# Audio_Codec_Analog_FrontEnd.net
KiCad netlist of a schematic drawn in Altium Designer
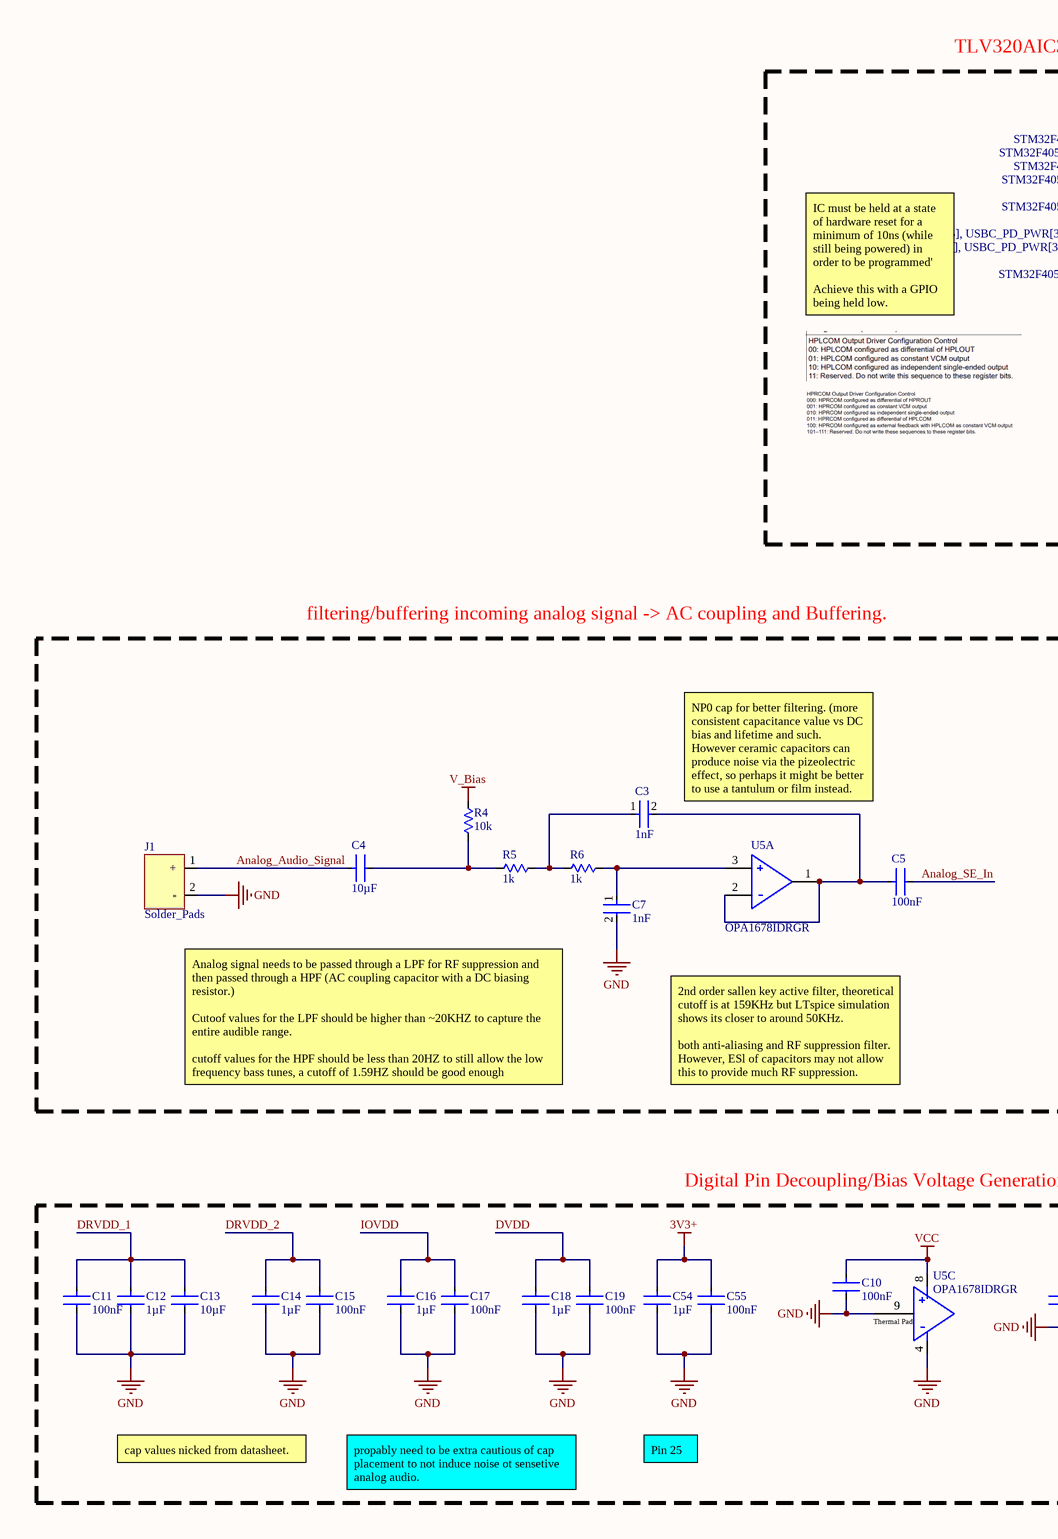
[diagram p0: Audio_Codec_Analog_FrontEnd.SchDoc, left]
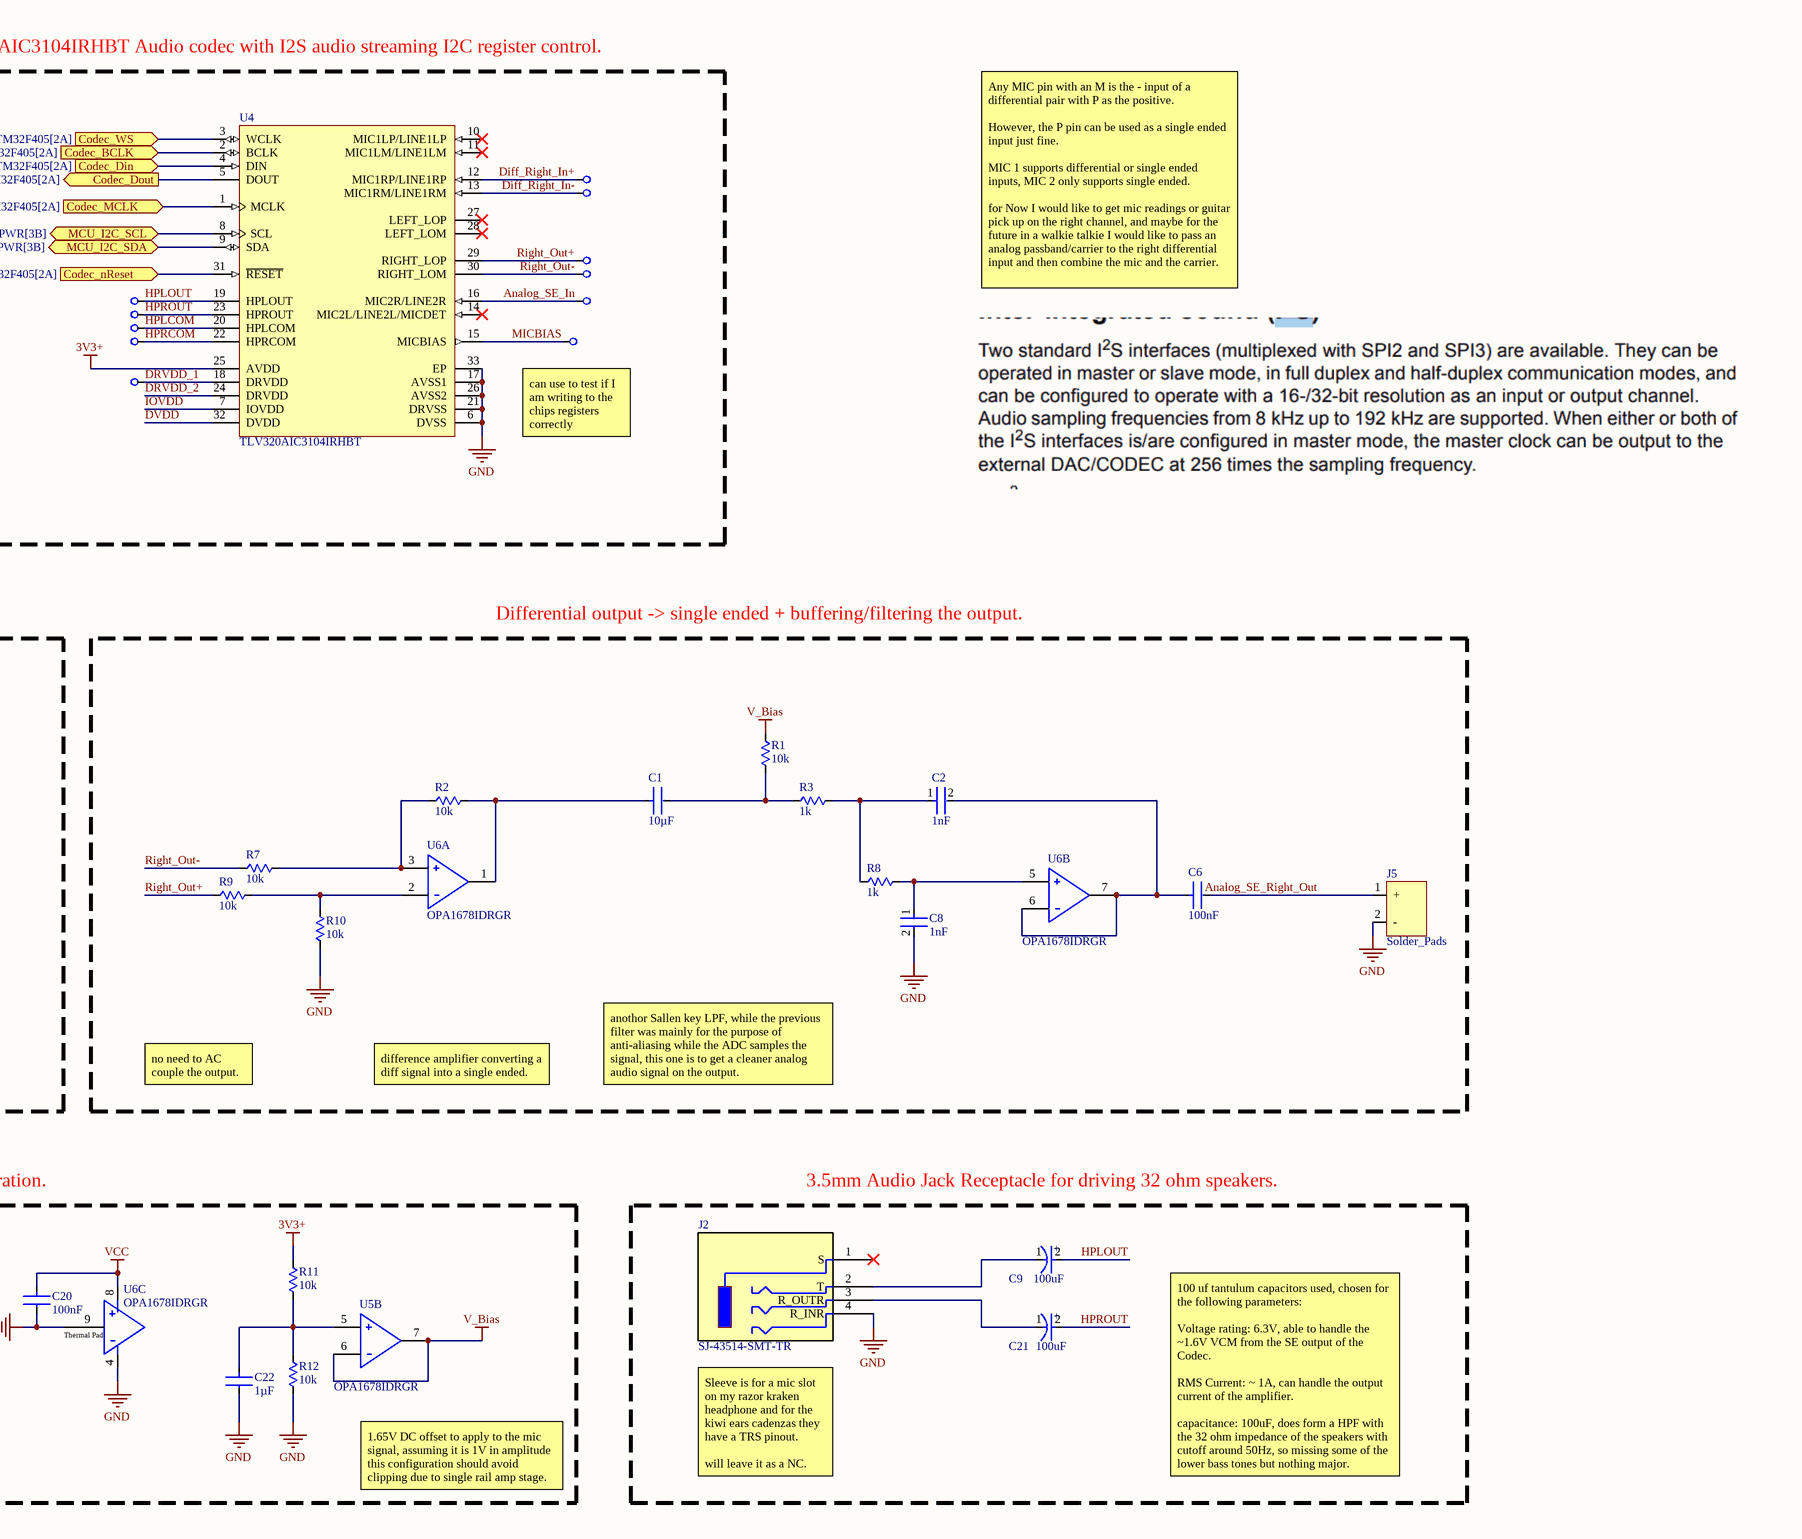
[diagram p1: Audio_Codec_Analog_FrontEnd.SchDoc, right]

(export (version "E")
  (design (tool "Eeschema 10.0.6"))
  (components
    (comp (ref "C1")
      (value "10µF")
      (footprint "MURATA-G_M21B")
      (description "10 µF ±10% 25V Ceramic Capacitor X7S 0805 (2012 Metric)")
      (fields (field (name "TOLERANCE") "10%") (field (name "Comment") "GCM21BC71E106KE36L"))
      (libsource (lib "UCalgary Racing") (part "CAPACITOR"))
    )
    (comp (ref "C2")
      (value "1nF")
      (footprint "FP-GRM188-0_1-e0_2_0_5-IPC_C")
      (description "Chip Multilayer Ceramic Capacitors for General Purpose, 0603, 1000pF, C0G, 30ppm/°C, 5%, 50V")
      (fields (field (name "TOLERANCE") "5%") (field (name "VOLTAGE") "50V"))
      (libsource (lib "Altium Content Vault") (part "11868f565c42a9108669ba33697ecf6"))
    )
    (comp (ref "C3")
      (value "1nF")
      (footprint "FP-GRM188-0_1-e0_2_0_5-IPC_C")
      (description "Chip Multilayer Ceramic Capacitors for General Purpose, 0603, 1000pF, C0G, 30ppm/°C, 5%, 50V")
      (fields (field (name "TOLERANCE") "5%") (field (name "VOLTAGE") "50V"))
      (libsource (lib "Altium Content Vault") (part "11868f565c42a9108669ba33697ecf6"))
    )
    (comp (ref "C4")
      (value "10µF")
      (footprint "MURATA-G_M21B")
      (description "10 µF ±10% 25V Ceramic Capacitor X7S 0805 (2012 Metric)")
      (fields (field (name "TOLERANCE") "10%") (field (name "Comment") "GCM21BC71E106KE36L"))
      (libsource (lib "UCalgary Racing") (part "CAPACITOR"))
    )
    (comp (ref "C5")
      (value "100nF")
      (footprint "MURATA-G_M188")
      (description "0.1 µF ±10% 50V Ceramic Capacitor X7R 0603 (1608 Metric)")
      (fields (field (name "TOLERANCE") "10%") (field (name "Comment") "GCM188R71H104KA57D"))
      (libsource (lib "UCalgary Racing") (part "CAPACITOR"))
    )
    (comp (ref "C6")
      (value "100nF")
      (footprint "MURATA-G_M188")
      (description "0.1 µF ±10% 50V Ceramic Capacitor X7R 0603 (1608 Metric)")
      (fields (field (name "TOLERANCE") "10%") (field (name "Comment") "GCM188R71H104KA57D"))
      (libsource (lib "UCalgary Racing") (part "CAPACITOR"))
    )
    (comp (ref "C7")
      (value "1nF")
      (footprint "FP-GRM188-0_1-e0_2_0_5-IPC_C")
      (description "Chip Multilayer Ceramic Capacitors for General Purpose, 0603, 1000pF, C0G, 30ppm/°C, 5%, 50V")
      (fields (field (name "TOLERANCE") "5%") (field (name "VOLTAGE") "50V"))
      (libsource (lib "Altium Content Vault") (part "11868f565c42a9108669ba33697ecf6"))
    )
    (comp (ref "C8")
      (value "1nF")
      (footprint "FP-GRM188-0_1-e0_2_0_5-IPC_C")
      (description "Chip Multilayer Ceramic Capacitors for General Purpose, 0603, 1000pF, C0G, 30ppm/°C, 5%, 50V")
      (fields (field (name "TOLERANCE") "5%") (field (name "VOLTAGE") "50V"))
      (libsource (lib "Altium Content Vault") (part "11868f565c42a9108669ba33697ecf6"))
    )
    (comp (ref "C9")
      (value "TAJB107M006RNJ")
      (footprint "FP-TAJB-MFG")
      (description "100uF 6.3V  ±20% 1.7Ω 1210  SMD Tantalum Capacitor")
      (fields (field (name "CAPACITANCE") "100uF") (field (name "TOLERANCE") "20%"))
      (libsource (lib "Altium Content Vault") (part "203bc49f2ac43e59fd269a8c329ed05"))
    )
    (comp (ref "C10")
      (value "100nF")
      (footprint "MURATA-G_M188")
      (description "0.1 µF ±10% 50V Ceramic Capacitor X7R 0603 (1608 Metric)")
      (fields (field (name "TOLERANCE") "10%") (field (name "Comment") "GCM188R71H104KA57D"))
      (libsource (lib "UCalgary Racing") (part "CAPACITOR"))
    )
    (comp (ref "C11")
      (value "100nF")
      (footprint "MURATA-G_M188")
      (description "0.1 µF ±10% 50V Ceramic Capacitor X7R 0603 (1608 Metric)")
      (fields (field (name "TOLERANCE") "10%") (field (name "Comment") "GCM188R71H104KA57D"))
      (libsource (lib "UCalgary Racing") (part "CAPACITOR"))
    )
    (comp (ref "C12")
      (value "1µF")
      (footprint "MURATA-G_M188")
      (description "1 µF ±10% 25V Ceramic Capacitor X7R 0603 (1608 Metric)")
      (fields (field (name "TOLERANCE") "10%") (field (name "Comment") "GCM188R71E105KA64D"))
      (libsource (lib "UCalgary Racing") (part "CAPACITOR"))
    )
    (comp (ref "C13")
      (value "10µF")
      (footprint "MURATA-G_M21B")
      (description "10 µF ±10% 25V Ceramic Capacitor X7S 0805 (2012 Metric)")
      (fields (field (name "TOLERANCE") "10%") (field (name "Comment") "GCM21BC71E106KE36L"))
      (libsource (lib "UCalgary Racing") (part "CAPACITOR"))
    )
    (comp (ref "C14")
      (value "1µF")
      (footprint "MURATA-G_M188")
      (description "1 µF ±10% 25V Ceramic Capacitor X7R 0603 (1608 Metric)")
      (fields (field (name "TOLERANCE") "10%") (field (name "Comment") "GCM188R71E105KA64D"))
      (libsource (lib "UCalgary Racing") (part "CAPACITOR"))
    )
    (comp (ref "C15")
      (value "100nF")
      (footprint "MURATA-G_M188")
      (description "0.1 µF ±10% 50V Ceramic Capacitor X7R 0603 (1608 Metric)")
      (fields (field (name "TOLERANCE") "10%") (field (name "Comment") "GCM188R71H104KA57D"))
      (libsource (lib "UCalgary Racing") (part "CAPACITOR"))
    )
    (comp (ref "C16")
      (value "1µF")
      (footprint "MURATA-G_M188")
      (description "1 µF ±10% 25V Ceramic Capacitor X7R 0603 (1608 Metric)")
      (fields (field (name "TOLERANCE") "10%") (field (name "Comment") "GCM188R71E105KA64D"))
      (libsource (lib "UCalgary Racing") (part "CAPACITOR"))
    )
    (comp (ref "C17")
      (value "100nF")
      (footprint "MURATA-G_M188")
      (description "0.1 µF ±10% 50V Ceramic Capacitor X7R 0603 (1608 Metric)")
      (fields (field (name "TOLERANCE") "10%") (field (name "Comment") "GCM188R71H104KA57D"))
      (libsource (lib "UCalgary Racing") (part "CAPACITOR"))
    )
    (comp (ref "C18")
      (value "1µF")
      (footprint "MURATA-G_M188")
      (description "1 µF ±10% 25V Ceramic Capacitor X7R 0603 (1608 Metric)")
      (fields (field (name "TOLERANCE") "10%") (field (name "Comment") "GCM188R71E105KA64D"))
      (libsource (lib "UCalgary Racing") (part "CAPACITOR"))
    )
    (comp (ref "C19")
      (value "100nF")
      (footprint "MURATA-G_M188")
      (description "0.1 µF ±10% 50V Ceramic Capacitor X7R 0603 (1608 Metric)")
      (fields (field (name "TOLERANCE") "10%") (field (name "Comment") "GCM188R71H104KA57D"))
      (libsource (lib "UCalgary Racing") (part "CAPACITOR"))
    )
    (comp (ref "C20")
      (value "100nF")
      (footprint "MURATA-G_M188")
      (description "0.1 µF ±10% 50V Ceramic Capacitor X7R 0603 (1608 Metric)")
      (fields (field (name "TOLERANCE") "10%") (field (name "Comment") "GCM188R71H104KA57D"))
      (libsource (lib "UCalgary Racing") (part "CAPACITOR"))
    )
    (comp (ref "C21")
      (value "TAJB107M006RNJ")
      (footprint "FP-TAJB-MFG")
      (description "100uF 6.3V  ±20% 1.7Ω 1210  SMD Tantalum Capacitor")
      (fields (field (name "CAPACITANCE") "100uF") (field (name "TOLERANCE") "20%"))
      (libsource (lib "Altium Content Vault") (part "203bc49f2ac43e59fd269a8c329ed05"))
    )
    (comp (ref "C22")
      (value "1µF")
      (footprint "MURATA-G_M188")
      (description "1 µF ±10% 25V Ceramic Capacitor X7R 0603 (1608 Metric)")
      (fields (field (name "TOLERANCE") "10%") (field (name "Comment") "GCM188R71E105KA64D"))
      (libsource (lib "UCalgary Racing") (part "CAPACITOR"))
    )
    (comp (ref "C54")
      (value "1µF")
      (footprint "MURATA-G_M188")
      (description "1 µF ±10% 25V Ceramic Capacitor X7R 0603 (1608 Metric)")
      (fields (field (name "TOLERANCE") "10%") (field (name "Comment") "GCM188R71E105KA64D"))
      (libsource (lib "UCalgary Racing") (part "CAPACITOR"))
    )
    (comp (ref "C55")
      (value "100nF")
      (footprint "MURATA-G_M188")
      (description "0.1 µF ±10% 50V Ceramic Capacitor X7R 0603 (1608 Metric)")
      (fields (field (name "TOLERANCE") "10%") (field (name "Comment") "GCM188R71H104KA57D"))
      (libsource (lib "UCalgary Racing") (part "CAPACITOR"))
    )
    (comp (ref "J1")
      (value "Solder_Pads")
      (footprint "2_soldering_pads")
      (libsource (lib "main_project_library") (part "Solder_Pads"))
    )
    (comp (ref "J2")
      (value "SJ-43514-SMT-TR")
      (footprint "SJ-43514-SMT_CUD")
      (description "Description")
      (fields (field (name "COPYRIGHT") "Copyright (C) 2025 Ultra Librarian. All rights reserved."))
      (libsource (lib "main_project_library") (part "SJ-43514-SMT-TR"))
    )
    (comp (ref "J5")
      (value "Solder_Pads")
      (footprint "2_soldering_pads")
      (libsource (lib "") (part "Solder_Pads_1"))
    )
    (comp (ref "R1")
      (value "10k")
      (footprint "VISHAY-CRCW0603")
      (description "10 kOhms ±1% 0.1W, 1/10W Chip Resistor 0603 (1608 Metric) Automotive AEC-Q200 Thick Film")
      (fields (field (name "POWER") "100mW") (field (name "TOLERANCE") "1%"))
      (libsource (lib "UCalgary Racing") (part "RESISTOR"))
    )
    (comp (ref "R2")
      (value "10k")
      (footprint "VISHAY-CRCW0603")
      (description "10 kOhms ±1% 0.1W, 1/10W Chip Resistor 0603 (1608 Metric) Automotive AEC-Q200 Thick Film")
      (fields (field (name "POWER") "100mW") (field (name "TOLERANCE") "1%"))
      (libsource (lib "UCalgary Racing") (part "RESISTOR"))
    )
    (comp (ref "R3")
      (value "1k")
      (footprint "VISHAY-TNPW0603")
      (fields
        (field (name "POWER") "100mW")
        (field (name "TOLERANCE") "0.1%")
        (field (name "Comment") "TNPW06031K00BEEA")
      )
      (libsource (lib "UCalgary Racing") (part "RESISTOR"))
    )
    (comp (ref "R4")
      (value "10k")
      (footprint "VISHAY-CRCW0603")
      (description "10 kOhms ±1% 0.1W, 1/10W Chip Resistor 0603 (1608 Metric) Automotive AEC-Q200 Thick Film")
      (fields (field (name "POWER") "100mW") (field (name "TOLERANCE") "1%"))
      (libsource (lib "UCalgary Racing") (part "RESISTOR"))
    )
    (comp (ref "R5")
      (value "1k")
      (footprint "VISHAY-TNPW0603")
      (fields
        (field (name "POWER") "100mW")
        (field (name "TOLERANCE") "0.1%")
        (field (name "Comment") "TNPW06031K00BEEA")
      )
      (libsource (lib "UCalgary Racing") (part "RESISTOR"))
    )
    (comp (ref "R6")
      (value "1k")
      (footprint "VISHAY-TNPW0603")
      (fields
        (field (name "POWER") "100mW")
        (field (name "TOLERANCE") "0.1%")
        (field (name "Comment") "TNPW06031K00BEEA")
      )
      (libsource (lib "UCalgary Racing") (part "RESISTOR"))
    )
    (comp (ref "R7")
      (value "10k")
      (footprint "VISHAY-CRCW0603")
      (description "10 kOhms ±1% 0.1W, 1/10W Chip Resistor 0603 (1608 Metric) Automotive AEC-Q200 Thick Film")
      (fields (field (name "POWER") "100mW") (field (name "TOLERANCE") "1%"))
      (libsource (lib "UCalgary Racing") (part "RESISTOR"))
    )
    (comp (ref "R8")
      (value "1k")
      (footprint "VISHAY-TNPW0603")
      (fields
        (field (name "POWER") "100mW")
        (field (name "TOLERANCE") "0.1%")
        (field (name "Comment") "TNPW06031K00BEEA")
      )
      (libsource (lib "UCalgary Racing") (part "RESISTOR"))
    )
    (comp (ref "R9")
      (value "10k")
      (footprint "VISHAY-CRCW0603")
      (description "10 kOhms ±1% 0.1W, 1/10W Chip Resistor 0603 (1608 Metric) Automotive AEC-Q200 Thick Film")
      (fields (field (name "POWER") "100mW") (field (name "TOLERANCE") "1%"))
      (libsource (lib "UCalgary Racing") (part "RESISTOR"))
    )
    (comp (ref "R10")
      (value "10k")
      (footprint "VISHAY-CRCW0603")
      (description "10 kOhms ±1% 0.1W, 1/10W Chip Resistor 0603 (1608 Metric) Automotive AEC-Q200 Thick Film")
      (fields (field (name "POWER") "100mW") (field (name "TOLERANCE") "1%"))
      (libsource (lib "UCalgary Racing") (part "RESISTOR"))
    )
    (comp (ref "R11")
      (value "10k")
      (footprint "VISHAY-CRCW0603")
      (description "10 kOhms ±1% 0.1W, 1/10W Chip Resistor 0603 (1608 Metric) Automotive AEC-Q200 Thick Film")
      (fields (field (name "POWER") "100mW") (field (name "TOLERANCE") "1%"))
      (libsource (lib "UCalgary Racing") (part "RESISTOR"))
    )
    (comp (ref "R12")
      (value "10k")
      (footprint "VISHAY-CRCW0603")
      (description "10 kOhms ±1% 0.1W, 1/10W Chip Resistor 0603 (1608 Metric) Automotive AEC-Q200 Thick Film")
      (fields (field (name "POWER") "100mW") (field (name "TOLERANCE") "1%"))
      (libsource (lib "UCalgary Racing") (part "RESISTOR"))
    )
    (comp (ref "TP1")
      (value "Testpoint 1mm")
      (footprint "Testpoint 1mm")
      (description "Labelled 1mm testpoint pad")
      (libsource (lib "UCalgary Racing") (part "Testpoint 1mm"))
    )
    (comp (ref "TP2")
      (value "Testpoint 1mm")
      (footprint "Testpoint 1mm")
      (description "Labelled 1mm testpoint pad")
      (libsource (lib "UCalgary Racing") (part "Testpoint 1mm"))
    )
    (comp (ref "TP3")
      (value "Testpoint 1mm")
      (footprint "Testpoint 1mm")
      (description "Labelled 1mm testpoint pad")
      (libsource (lib "UCalgary Racing") (part "Testpoint 1mm"))
    )
    (comp (ref "TP4")
      (value "Testpoint 1mm")
      (footprint "Testpoint 1mm")
      (description "Labelled 1mm testpoint pad")
      (libsource (lib "UCalgary Racing") (part "Testpoint 1mm"))
    )
    (comp (ref "TP5")
      (value "Testpoint 1mm")
      (footprint "Testpoint 1mm")
      (description "Labelled 1mm testpoint pad")
      (libsource (lib "UCalgary Racing") (part "Testpoint 1mm"))
    )
    (comp (ref "TP6")
      (value "Testpoint 1mm")
      (footprint "Testpoint 1mm")
      (description "Labelled 1mm testpoint pad")
      (libsource (lib "UCalgary Racing") (part "Testpoint 1mm"))
    )
    (comp (ref "TP7")
      (value "Testpoint 1mm")
      (footprint "Testpoint 1mm")
      (description "Labelled 1mm testpoint pad")
      (libsource (lib "UCalgary Racing") (part "Testpoint 1mm"))
    )
    (comp (ref "TP8")
      (value "Testpoint 1mm")
      (footprint "Testpoint 1mm")
      (description "Labelled 1mm testpoint pad")
      (libsource (lib "UCalgary Racing") (part "Testpoint 1mm"))
    )
    (comp (ref "TP9")
      (value "Testpoint 1mm")
      (footprint "Testpoint 1mm")
      (description "Labelled 1mm testpoint pad")
      (libsource (lib "UCalgary Racing") (part "Testpoint 1mm"))
    )
    (comp (ref "TP25")
      (value "Testpoint 1mm")
      (footprint "Testpoint 1mm")
      (description "Labelled 1mm testpoint pad")
      (libsource (lib "UCalgary Racing") (part "Testpoint 1mm"))
    )
    (comp (ref "TP26")
      (value "Testpoint 1mm")
      (footprint "Testpoint 1mm")
      (description "Labelled 1mm testpoint pad")
      (libsource (lib "UCalgary Racing") (part "Testpoint 1mm"))
    )
    (comp (ref "U4")
      (value "TLV320AIC3104IRHBT")
      (footprint "RHB0032E_V")
      (fields (field (name "MANUFACTURER") "Texas Instruments"))
      (libsource (lib "Altium Content Vault") (part "TI-TLV320AIC3104RHB32-3450X3450TP"))
    )
    (comp (ref "U5")
      (value "OPA1678IDRGR")
      (footprint "FP-DRG0008A-IPC_B")
      (description "IC AUDIO 2 CIRCUIT 8SON")
      (libsource (lib "main_project_library") (part "CMP-04894-000047-1"))
    )
    (comp (ref "U6")
      (value "OPA1678IDRGR")
      (footprint "FP-DRG0008A-IPC_B")
      (description "IC AUDIO 2 CIRCUIT 8SON")
      (libsource (lib "main_project_library") (part "CMP-04894-000047-1"))
    )
  )
  (nets
    (net (code "1") (name "/Analog_Audio_Signal") (class "Default")
      (node (ref "C4") (pin "1") (pinfunction "1_1") (pintype "passive"))
      (node (ref "J1") (pin "1") (pinfunction "+_1") (pintype "passive"))
    )
    (net (code "2") (name "/Analog_SE_In") (class "Default")
      (node (ref "C5") (pin "2") (pinfunction "2_2") (pintype "passive"))
      (node (ref "TP6") (pin "1") (pinfunction "1_1") (pintype "passive"))
      (node (ref "U4") (pin "16") (pinfunction "MIC2R/LINE2R_16") (pintype "input"))
    )
    (net (code "3") (name "/Analog_SE_Right_Out") (class "Default")
      (node (ref "C6") (pin "2") (pinfunction "2_2") (pintype "passive"))
      (node (ref "J5") (pin "1") (pinfunction "+_1") (pintype "passive"))
    )
    (net (code "4") (name "/Codec_BCLK") (class "Default")
      (node (ref "U4") (pin "2") (pinfunction "BCLK_2") (pintype "bidirectional"))
    )
    (net (code "5") (name "/Codec_Din") (class "Default")
      (node (ref "U4") (pin "4") (pinfunction "DIN_4") (pintype "input"))
    )
    (net (code "6") (name "/Codec_Dout") (class "Default")
      (node (ref "U4") (pin "5") (pinfunction "DOUT_5") (pintype "tri_state"))
    )
    (net (code "7") (name "/Codec_MCLK") (class "Default")
      (node (ref "U4") (pin "1") (pinfunction "MCLK_1") (pintype "input"))
    )
    (net (code "8") (name "/Codec_WS") (class "Default")
      (node (ref "U4") (pin "3") (pinfunction "WCLK_3") (pintype "bidirectional"))
    )
    (net (code "9") (name "/Codec_nReset") (class "Default")
      (node (ref "U4") (pin "31") (pinfunction "~{RESET}_31") (pintype "input"))
    )
    (net (code "10") (name "/DRVDD_1") (class "Default")
      (node (ref "C11") (pin "1") (pinfunction "1_1") (pintype "passive"))
      (node (ref "C12") (pin "1") (pinfunction "1_1") (pintype "passive"))
      (node (ref "C13") (pin "1") (pinfunction "1_1") (pintype "passive"))
      (node (ref "TP9") (pin "1") (pinfunction "1_1") (pintype "passive"))
      (node (ref "U4") (pin "18") (pinfunction "DRVDD_18") (pintype "power_in"))
    )
    (net (code "11") (name "/DRVDD_2") (class "Default")
      (node (ref "C14") (pin "1") (pinfunction "1_1") (pintype "passive"))
      (node (ref "C15") (pin "1") (pinfunction "1_1") (pintype "passive"))
      (node (ref "U4") (pin "24") (pinfunction "DRVDD_24") (pintype "power_in"))
    )
    (net (code "12") (name "/DVDD") (class "Default")
      (node (ref "C18") (pin "1") (pinfunction "1_1") (pintype "passive"))
      (node (ref "C19") (pin "1") (pinfunction "1_1") (pintype "passive"))
      (node (ref "U4") (pin "32") (pinfunction "DVDD_32") (pintype "power_in"))
    )
    (net (code "13") (name "/Diff_Right_In+") (class "Default")
      (node (ref "TP1") (pin "1") (pinfunction "1_1") (pintype "passive"))
      (node (ref "U4") (pin "12") (pinfunction "MIC1RP/LINE1RP_12") (pintype "input"))
    )
    (net (code "14") (name "/Diff_Right_In-") (class "Default")
      (node (ref "TP2") (pin "1") (pinfunction "1_1") (pintype "passive"))
      (node (ref "U4") (pin "13") (pinfunction "MIC1RM/LINE1RM_13") (pintype "input"))
    )
    (net (code "15") (name "/HPLCOM") (class "Default")
      (node (ref "TP25") (pin "1") (pinfunction "1_1") (pintype "passive"))
      (node (ref "U4") (pin "20") (pinfunction "HPLCOM_20") (pintype "tri_state"))
    )
    (net (code "16") (name "/HPLOUT") (class "Default")
      (node (ref "C9") (pin "2") (pinfunction "A_2") (pintype "passive"))
      (node (ref "TP5") (pin "1") (pinfunction "1_1") (pintype "passive"))
      (node (ref "U4") (pin "19") (pinfunction "HPLOUT_19") (pintype "tri_state"))
    )
    (net (code "17") (name "/HPRCOM") (class "Default")
      (node (ref "TP26") (pin "1") (pinfunction "1_1") (pintype "passive"))
      (node (ref "U4") (pin "22") (pinfunction "HPRCOM_22") (pintype "tri_state"))
    )
    (net (code "18") (name "/HPROUT") (class "Default")
      (node (ref "C21") (pin "2") (pinfunction "A_2") (pintype "passive"))
      (node (ref "TP7") (pin "1") (pinfunction "1_1") (pintype "passive"))
      (node (ref "U4") (pin "23") (pinfunction "HPROUT_23") (pintype "tri_state"))
    )
    (net (code "19") (name "/IOVDD") (class "Default")
      (node (ref "C16") (pin "1") (pinfunction "1_1") (pintype "passive"))
      (node (ref "C17") (pin "1") (pinfunction "1_1") (pintype "passive"))
      (node (ref "U4") (pin "7") (pinfunction "IOVDD_7") (pintype "power_in"))
    )
    (net (code "20") (name "/MCU_I2C_SCL") (class "Default")
      (node (ref "U4") (pin "8") (pinfunction "SCL_8") (pintype "input"))
    )
    (net (code "21") (name "/MCU_I2C_SDA") (class "Default")
      (node (ref "U4") (pin "9") (pinfunction "SDA_9") (pintype "bidirectional"))
    )
    (net (code "22") (name "/MICBIAS") (class "Default")
      (node (ref "TP8") (pin "1") (pinfunction "1_1") (pintype "passive"))
      (node (ref "U4") (pin "15") (pinfunction "MICBIAS_15") (pintype "output"))
    )
    (net (code "23") (name "/Right_Out+") (class "Default")
      (node (ref "R9") (pin "2") (pinfunction "2_2") (pintype "passive"))
      (node (ref "TP3") (pin "1") (pinfunction "1_1") (pintype "passive"))
      (node (ref "U4") (pin "29") (pinfunction "RIGHT_LOP_29") (pintype "tri_state"))
    )
    (net (code "24") (name "/Right_Out-") (class "Default")
      (node (ref "R7") (pin "2") (pinfunction "2_2") (pintype "passive"))
      (node (ref "TP4") (pin "1") (pinfunction "1_1") (pintype "passive"))
      (node (ref "U4") (pin "30") (pinfunction "RIGHT_LOM_30") (pintype "tri_state"))
    )
    (net (code "25") (name "3V3+") (class "Default")
      (node (ref "C54") (pin "1") (pinfunction "1_1") (pintype "passive"))
      (node (ref "C55") (pin "1") (pinfunction "1_1") (pintype "passive"))
      (node (ref "R11") (pin "2") (pinfunction "2_2") (pintype "passive"))
      (node (ref "U4") (pin "25") (pinfunction "AVDD_25") (pintype "power_in"))
    )
    (net (code "26") (name "GND") (class "Default")
      (node (ref "C10") (pin "2") (pinfunction "2_2") (pintype "passive"))
      (node (ref "C11") (pin "2") (pinfunction "2_2") (pintype "passive"))
      (node (ref "C12") (pin "2") (pinfunction "2_2") (pintype "passive"))
      (node (ref "C13") (pin "2") (pinfunction "2_2") (pintype "passive"))
      (node (ref "C14") (pin "2") (pinfunction "2_2") (pintype "passive"))
      (node (ref "C15") (pin "2") (pinfunction "2_2") (pintype "passive"))
      (node (ref "C16") (pin "2") (pinfunction "2_2") (pintype "passive"))
      (node (ref "C17") (pin "2") (pinfunction "2_2") (pintype "passive"))
      (node (ref "C18") (pin "2") (pinfunction "2_2") (pintype "passive"))
      (node (ref "C19") (pin "2") (pinfunction "2_2") (pintype "passive"))
      (node (ref "C20") (pin "2") (pinfunction "2_2") (pintype "passive"))
      (node (ref "C22") (pin "2") (pinfunction "2_2") (pintype "passive"))
      (node (ref "C54") (pin "2") (pinfunction "2_2") (pintype "passive"))
      (node (ref "C55") (pin "2") (pinfunction "2_2") (pintype "passive"))
      (node (ref "C7") (pin "2") (pinfunction "2_2") (pintype "passive"))
      (node (ref "C8") (pin "2") (pinfunction "2_2") (pintype "passive"))
      (node (ref "J1") (pin "2") (pinfunction "-_2") (pintype "passive"))
      (node (ref "J2") (pin "4") (pinfunction "R_INR_4") (pintype "passive"))
      (node (ref "J5") (pin "2") (pinfunction "-_2") (pintype "passive"))
      (node (ref "R10") (pin "2") (pinfunction "2_2") (pintype "passive"))
      (node (ref "R12") (pin "1") (pinfunction "1_1") (pintype "passive"))
      (node (ref "U4") (pin "17") (pinfunction "AVSS1_17") (pintype "power_in"))
      (node (ref "U4") (pin "21") (pinfunction "DRVSS_21") (pintype "power_in"))
      (node (ref "U4") (pin "26") (pinfunction "AVSS2_26") (pintype "power_in"))
      (node (ref "U4") (pin "33") (pinfunction "EP_33") (pintype "power_in"))
      (node (ref "U4") (pin "6") (pinfunction "DVSS_6") (pintype "power_in"))
      (node (ref "U5") (pin "4") (pinfunction "OUT_B_4") (pintype "passive"))
      (node (ref "U5") (pin "9") (pinfunction "Thermal_Pad_9") (pintype "passive"))
      (node (ref "U6") (pin "4") (pinfunction "OUT_B_4") (pintype "passive"))
      (node (ref "U6") (pin "9") (pinfunction "Thermal_Pad_9") (pintype "passive"))
    )
    (net (code "27") (name "Net-(C1-Pad2)") (class "Default")
      (node (ref "C1") (pin "2") (pinfunction "2_2") (pintype "passive"))
      (node (ref "R1") (pin "1") (pinfunction "1_1") (pintype "passive"))
      (node (ref "R3") (pin "2") (pinfunction "2_2") (pintype "passive"))
    )
    (net (code "28") (name "Net-(C2-Pad1)") (class "Default")
      (node (ref "C2") (pin "1") (pinfunction "1_1") (pintype "passive"))
      (node (ref "R3") (pin "1") (pinfunction "1_1") (pintype "passive"))
      (node (ref "R8") (pin "2") (pinfunction "2_2") (pintype "passive"))
    )
    (net (code "29") (name "Net-(C3-Pad1)") (class "Default")
      (node (ref "C3") (pin "1") (pinfunction "1_1") (pintype "passive"))
      (node (ref "R5") (pin "1") (pinfunction "1_1") (pintype "passive"))
      (node (ref "R6") (pin "2") (pinfunction "2_2") (pintype "passive"))
    )
    (net (code "30") (name "Net-(C4-Pad2)") (class "Default")
      (node (ref "C4") (pin "2") (pinfunction "2_2") (pintype "passive"))
      (node (ref "R4") (pin "1") (pinfunction "1_1") (pintype "passive"))
      (node (ref "R5") (pin "2") (pinfunction "2_2") (pintype "passive"))
    )
    (net (code "31") (name "Net-(C9-C)") (class "Default")
      (node (ref "C9") (pin "1") (pinfunction "C_1") (pintype "passive"))
      (node (ref "J2") (pin "2") (pinfunction "T_2") (pintype "passive"))
    )
    (net (code "32") (name "Net-(C21-C)") (class "Default")
      (node (ref "C21") (pin "1") (pinfunction "C_1") (pintype "passive"))
      (node (ref "J2") (pin "3") (pinfunction "R_OUTR_3") (pintype "passive"))
    )
    (net (code "33") (name "Net-(U5A-+IN_B)") (class "Default")
      (node (ref "C7") (pin "1") (pinfunction "1_1") (pintype "passive"))
      (node (ref "R6") (pin "1") (pinfunction "1_1") (pintype "passive"))
      (node (ref "U5") (pin "3") (pinfunction "+IN_B_3") (pintype "tri_state"))
    )
    (net (code "34") (name "Net-(U5A--IN_B)") (class "Default")
      (node (ref "C3") (pin "2") (pinfunction "2_2") (pintype "passive"))
      (node (ref "C5") (pin "1") (pinfunction "1_1") (pintype "passive"))
      (node (ref "U5") (pin "1") (pinfunction "OUT_B_1") (pintype "passive"))
      (node (ref "U5") (pin "2") (pinfunction "-IN_B_2") (pintype "tri_state"))
    )
    (net (code "35") (name "Net-(U5B-+IN_B)") (class "Default")
      (node (ref "C22") (pin "1") (pinfunction "1_1") (pintype "passive"))
      (node (ref "R11") (pin "1") (pinfunction "1_1") (pintype "passive"))
      (node (ref "R12") (pin "2") (pinfunction "2_2") (pintype "passive"))
      (node (ref "U5") (pin "5") (pinfunction "+IN_B_5") (pintype "tri_state"))
    )
    (net (code "36") (name "Net-(U6A-+IN_B)") (class "Default")
      (node (ref "R2") (pin "2") (pinfunction "2_2") (pintype "passive"))
      (node (ref "R7") (pin "1") (pinfunction "1_1") (pintype "passive"))
      (node (ref "U6") (pin "3") (pinfunction "+IN_B_3") (pintype "tri_state"))
    )
    (net (code "37") (name "Net-(U6A--IN_B)") (class "Default")
      (node (ref "R10") (pin "1") (pinfunction "1_1") (pintype "passive"))
      (node (ref "R9") (pin "1") (pinfunction "1_1") (pintype "passive"))
      (node (ref "U6") (pin "2") (pinfunction "-IN_B_2") (pintype "tri_state"))
    )
    (net (code "38") (name "Net-(U6A-OUT_B)") (class "Default")
      (node (ref "C1") (pin "1") (pinfunction "1_1") (pintype "passive"))
      (node (ref "R2") (pin "1") (pinfunction "1_1") (pintype "passive"))
      (node (ref "U6") (pin "1") (pinfunction "OUT_B_1") (pintype "passive"))
    )
    (net (code "39") (name "Net-(U6B-+IN_B)") (class "Default")
      (node (ref "C8") (pin "1") (pinfunction "1_1") (pintype "passive"))
      (node (ref "R8") (pin "1") (pinfunction "1_1") (pintype "passive"))
      (node (ref "U6") (pin "5") (pinfunction "+IN_B_5") (pintype "tri_state"))
    )
    (net (code "40") (name "Net-(U6B--IN_B)") (class "Default")
      (node (ref "C2") (pin "2") (pinfunction "2_2") (pintype "passive"))
      (node (ref "C6") (pin "1") (pinfunction "1_1") (pintype "passive"))
      (node (ref "U6") (pin "6") (pinfunction "-IN_B_6") (pintype "tri_state"))
      (node (ref "U6") (pin "7") (pinfunction "OUT_B_7") (pintype "passive"))
    )
    (net (code "41") (name "VCC") (class "Default")
      (node (ref "C10") (pin "1") (pinfunction "1_1") (pintype "passive"))
      (node (ref "C20") (pin "1") (pinfunction "1_1") (pintype "passive"))
      (node (ref "U5") (pin "8") (pinfunction "OUT_B_8") (pintype "passive"))
      (node (ref "U6") (pin "8") (pinfunction "OUT_B_8") (pintype "passive"))
    )
    (net (code "42") (name "V_Bias") (class "Default")
      (node (ref "R1") (pin "2") (pinfunction "2_2") (pintype "passive"))
      (node (ref "R4") (pin "2") (pinfunction "2_2") (pintype "passive"))
      (node (ref "U5") (pin "6") (pinfunction "-IN_B_6") (pintype "tri_state"))
      (node (ref "U5") (pin "7") (pinfunction "OUT_B_7") (pintype "passive"))
    )
    (net (code "43") (name "unconnected-(J2-S-Pad1)") (class "Default")
      (node (ref "J2") (pin "1") (pinfunction "S_1") (pintype "passive+no_connect"))
    )
    (net (code "44") (name "unconnected-(U4-LEFT_LOM-Pad28)") (class "Default")
      (node (ref "U4") (pin "28") (pinfunction "LEFT_LOM_28") (pintype "tri_state+no_connect"))
    )
    (net (code "45") (name "unconnected-(U4-LEFT_LOP-Pad27)") (class "Default")
      (node (ref "U4") (pin "27") (pinfunction "LEFT_LOP_27") (pintype "tri_state+no_connect"))
    )
    (net (code "46") (name "unconnected-(U4-MIC1LM{slash}LINE1LM-Pad11)") (class "Default")
      (node (ref "U4") (pin "11") (pinfunction "MIC1LM/LINE1LM_11") (pintype "input+no_connect"))
    )
    (net (code "47") (name "unconnected-(U4-MIC1LP{slash}LINE1LP-Pad10)") (class "Default")
      (node (ref "U4") (pin "10") (pinfunction "MIC1LP/LINE1LP_10") (pintype "input+no_connect"))
    )
    (net (code "48") (name "unconnected-(U4-MIC2L{slash}LINE2L{slash}MICDET-Pad14)") (class "Default")
      (node (ref "U4") (pin "14") (pinfunction "MIC2L/LINE2L/MICDET_14") (pintype "input+no_connect"))
    )
  )
)
